# SoC_Power.net
KiCad netlist of a schematic drawn in Altium Designer
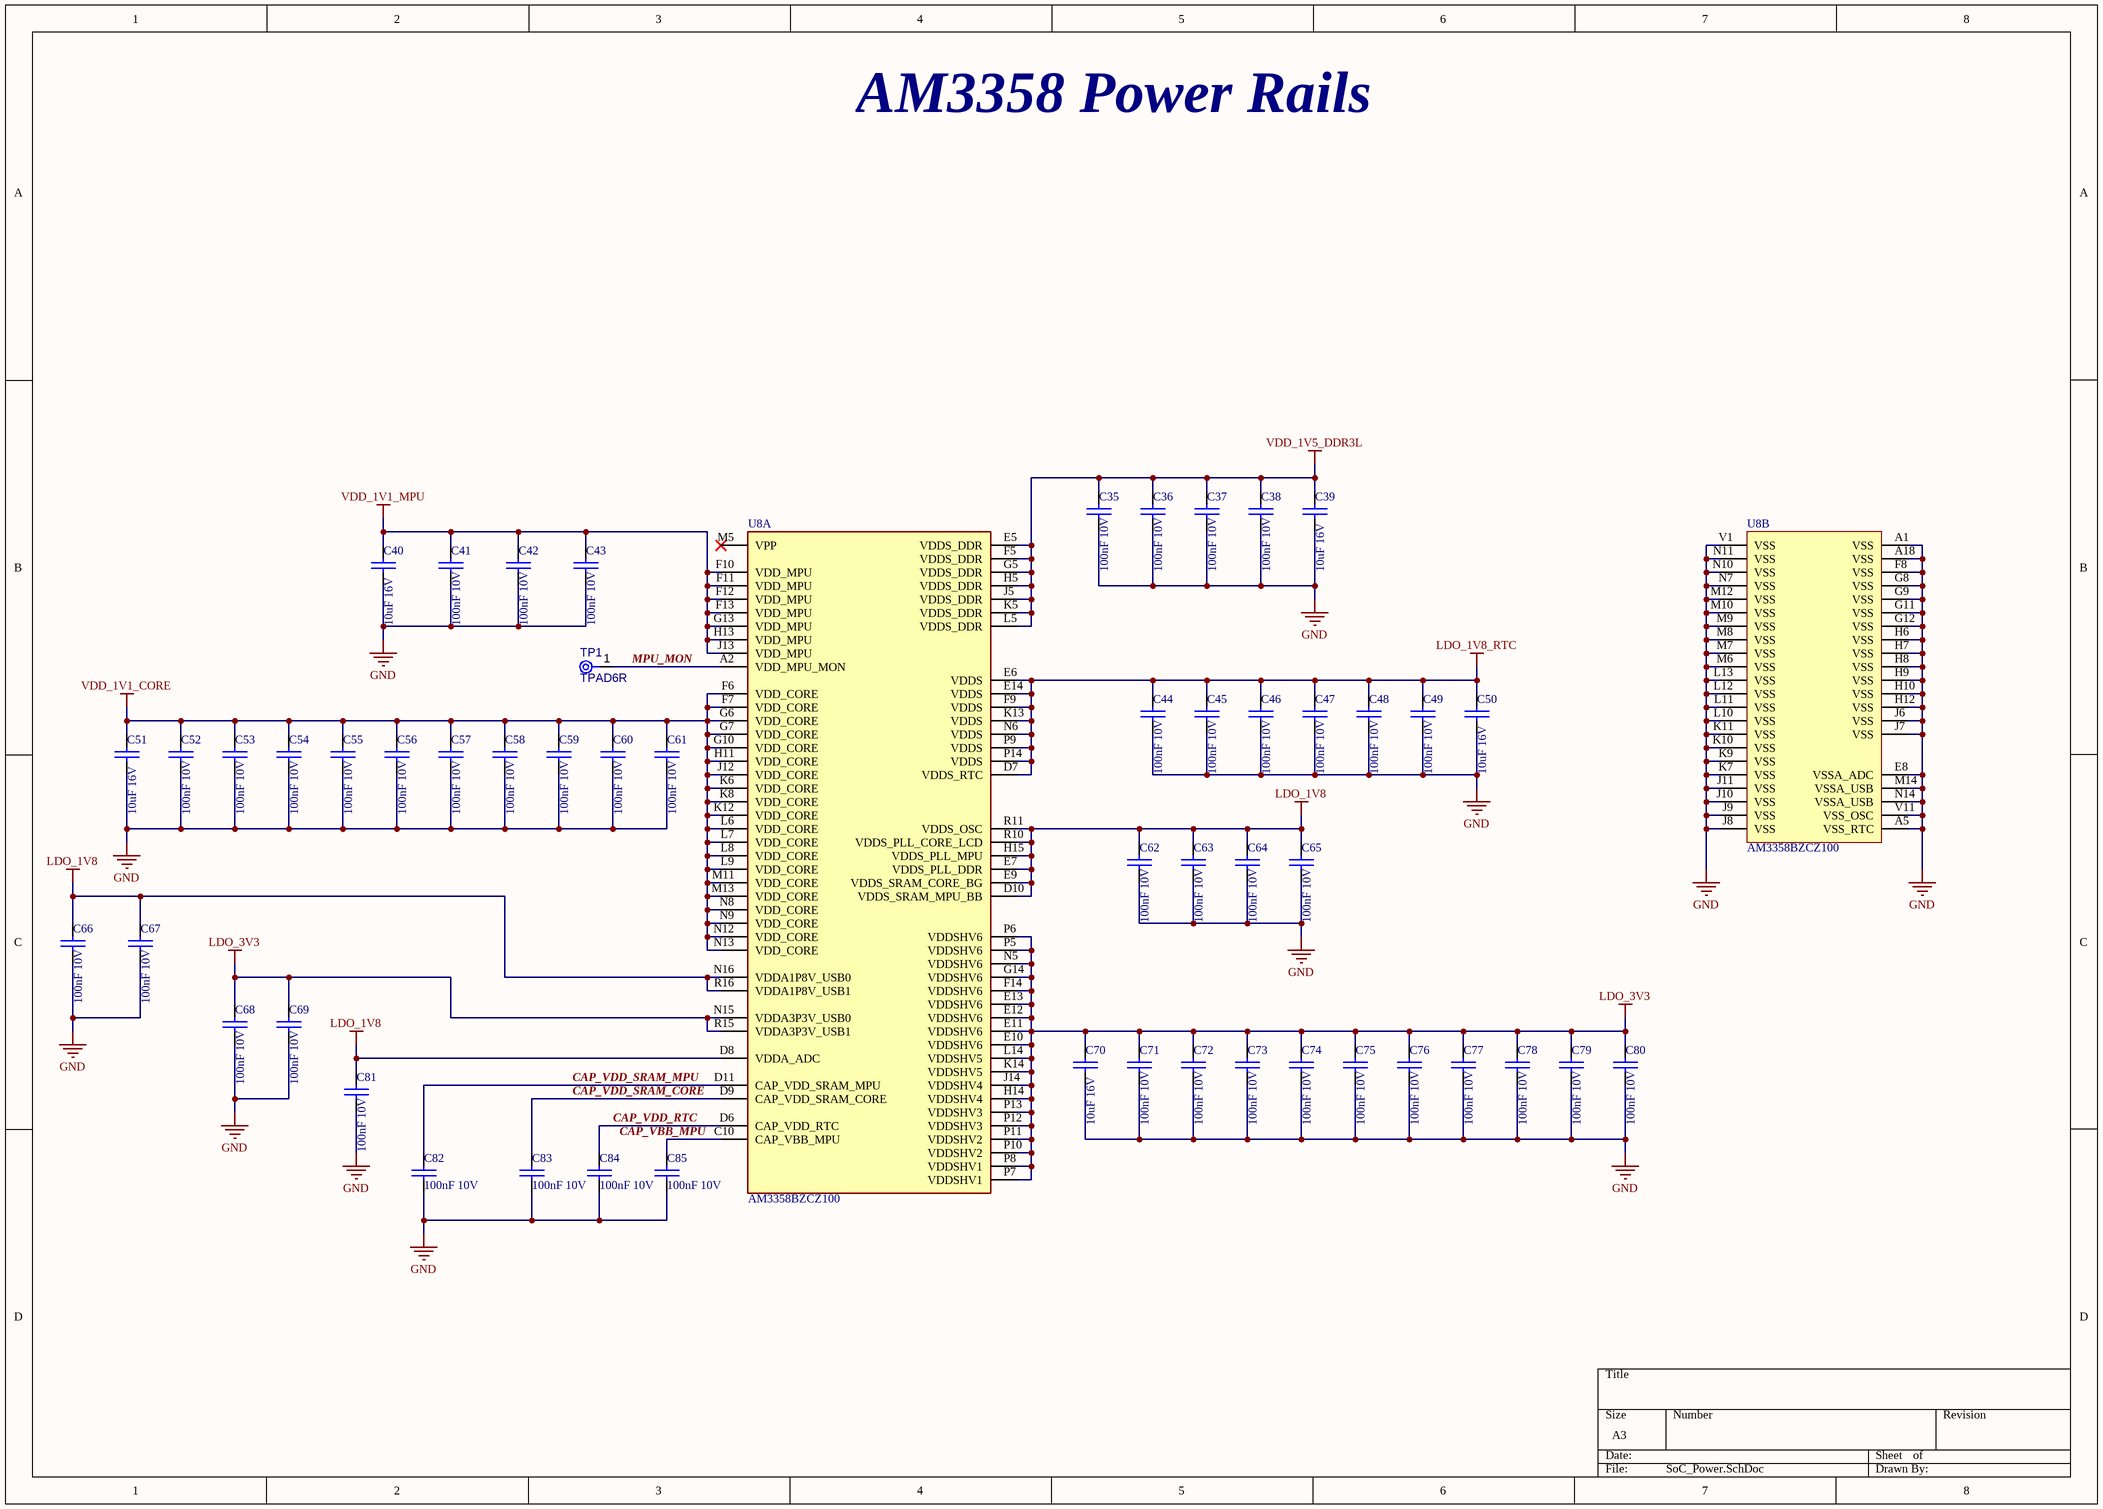
[diagram p0: SoC_Power.SchDoc]

(export (version "E")
  (design (tool "Eeschema 10.0.6"))
  (components
    (comp (ref "C35")
      (value "100nF 10V")
      (footprint "C_0201")
      (description "Capacitor 0201 SMD")
      (libsource (lib "tor1kkLib") (part "C_0201"))
    )
    (comp (ref "C36")
      (value "100nF 10V")
      (footprint "C_0201")
      (description "Capacitor 0201 SMD")
      (libsource (lib "tor1kkLib") (part "C_0201"))
    )
    (comp (ref "C37")
      (value "100nF 10V")
      (footprint "C_0201")
      (description "Capacitor 0201 SMD")
      (libsource (lib "tor1kkLib") (part "C_0201"))
    )
    (comp (ref "C38")
      (value "100nF 10V")
      (footprint "C_0201")
      (description "Capacitor 0201 SMD")
      (libsource (lib "tor1kkLib") (part "C_0201"))
    )
    (comp (ref "C39")
      (value "10uF 16V")
      (footprint "C_0603")
      (description "Capacitor 0603 SMD")
      (libsource (lib "tor1kkLib") (part "C_0603"))
    )
    (comp (ref "C40")
      (value "10uF 16V")
      (footprint "C_0603")
      (description "Capacitor 0603 SMD")
      (libsource (lib "tor1kkLib") (part "C_0603"))
    )
    (comp (ref "C41")
      (value "100nF 10V")
      (footprint "C_0201")
      (description "Capacitor 0201 SMD")
      (libsource (lib "tor1kkLib") (part "C_0201"))
    )
    (comp (ref "C42")
      (value "100nF 10V")
      (footprint "C_0201")
      (description "Capacitor 0201 SMD")
      (libsource (lib "tor1kkLib") (part "C_0201"))
    )
    (comp (ref "C43")
      (value "100nF 10V")
      (footprint "C_0201")
      (description "Capacitor 0201 SMD")
      (libsource (lib "tor1kkLib") (part "C_0201"))
    )
    (comp (ref "C44")
      (value "100nF 10V")
      (footprint "C_0201")
      (description "Capacitor 0201 SMD")
      (libsource (lib "tor1kkLib") (part "C_0201"))
    )
    (comp (ref "C45")
      (value "100nF 10V")
      (footprint "C_0201")
      (description "Capacitor 0201 SMD")
      (libsource (lib "tor1kkLib") (part "C_0201"))
    )
    (comp (ref "C46")
      (value "100nF 10V")
      (footprint "C_0201")
      (description "Capacitor 0201 SMD")
      (libsource (lib "tor1kkLib") (part "C_0201"))
    )
    (comp (ref "C47")
      (value "100nF 10V")
      (footprint "C_0201")
      (description "Capacitor 0201 SMD")
      (libsource (lib "tor1kkLib") (part "C_0201"))
    )
    (comp (ref "C48")
      (value "100nF 10V")
      (footprint "C_0201")
      (description "Capacitor 0201 SMD")
      (libsource (lib "tor1kkLib") (part "C_0201"))
    )
    (comp (ref "C49")
      (value "100nF 10V")
      (footprint "C_0201")
      (description "Capacitor 0201 SMD")
      (libsource (lib "tor1kkLib") (part "C_0201"))
    )
    (comp (ref "C50")
      (value "10uF 16V")
      (footprint "C_0603")
      (description "Capacitor 0603 SMD")
      (libsource (lib "tor1kkLib") (part "C_0603"))
    )
    (comp (ref "C51")
      (value "10uF 16V")
      (footprint "C_0603")
      (description "Capacitor 0603 SMD")
      (libsource (lib "tor1kkLib") (part "C_0603"))
    )
    (comp (ref "C52")
      (value "100nF 10V")
      (footprint "C_0201")
      (description "Capacitor 0201 SMD")
      (libsource (lib "tor1kkLib") (part "C_0201"))
    )
    (comp (ref "C53")
      (value "100nF 10V")
      (footprint "C_0201")
      (description "Capacitor 0201 SMD")
      (libsource (lib "tor1kkLib") (part "C_0201"))
    )
    (comp (ref "C54")
      (value "100nF 10V")
      (footprint "C_0201")
      (description "Capacitor 0201 SMD")
      (libsource (lib "tor1kkLib") (part "C_0201"))
    )
    (comp (ref "C55")
      (value "100nF 10V")
      (footprint "C_0201")
      (description "Capacitor 0201 SMD")
      (libsource (lib "tor1kkLib") (part "C_0201"))
    )
    (comp (ref "C56")
      (value "100nF 10V")
      (footprint "C_0201")
      (description "Capacitor 0201 SMD")
      (libsource (lib "tor1kkLib") (part "C_0201"))
    )
    (comp (ref "C57")
      (value "100nF 10V")
      (footprint "C_0201")
      (description "Capacitor 0201 SMD")
      (libsource (lib "tor1kkLib") (part "C_0201"))
    )
    (comp (ref "C58")
      (value "100nF 10V")
      (footprint "C_0201")
      (description "Capacitor 0201 SMD")
      (libsource (lib "tor1kkLib") (part "C_0201"))
    )
    (comp (ref "C59")
      (value "100nF 10V")
      (footprint "C_0201")
      (description "Capacitor 0201 SMD")
      (libsource (lib "tor1kkLib") (part "C_0201"))
    )
    (comp (ref "C60")
      (value "100nF 10V")
      (footprint "C_0201")
      (description "Capacitor 0201 SMD")
      (libsource (lib "tor1kkLib") (part "C_0201"))
    )
    (comp (ref "C61")
      (value "100nF 10V")
      (footprint "C_0201")
      (description "Capacitor 0201 SMD")
      (libsource (lib "tor1kkLib") (part "C_0201"))
    )
    (comp (ref "C62")
      (value "100nF 10V")
      (footprint "C_0201")
      (description "Capacitor 0201 SMD")
      (libsource (lib "tor1kkLib") (part "C_0201"))
    )
    (comp (ref "C63")
      (value "100nF 10V")
      (footprint "C_0201")
      (description "Capacitor 0201 SMD")
      (libsource (lib "tor1kkLib") (part "C_0201"))
    )
    (comp (ref "C64")
      (value "100nF 10V")
      (footprint "C_0201")
      (description "Capacitor 0201 SMD")
      (libsource (lib "tor1kkLib") (part "C_0201"))
    )
    (comp (ref "C65")
      (value "100nF 10V")
      (footprint "C_0201")
      (description "Capacitor 0201 SMD")
      (libsource (lib "tor1kkLib") (part "C_0201"))
    )
    (comp (ref "C66")
      (value "100nF 10V")
      (footprint "C_0201")
      (description "Capacitor 0201 SMD")
      (libsource (lib "tor1kkLib") (part "C_0201"))
    )
    (comp (ref "C67")
      (value "100nF 10V")
      (footprint "C_0201")
      (description "Capacitor 0201 SMD")
      (libsource (lib "tor1kkLib") (part "C_0201"))
    )
    (comp (ref "C68")
      (value "100nF 10V")
      (footprint "C_0201")
      (description "Capacitor 0201 SMD")
      (libsource (lib "tor1kkLib") (part "C_0201"))
    )
    (comp (ref "C69")
      (value "100nF 10V")
      (footprint "C_0201")
      (description "Capacitor 0201 SMD")
      (libsource (lib "tor1kkLib") (part "C_0201"))
    )
    (comp (ref "C70")
      (value "10uF 16V")
      (footprint "C_0603")
      (description "Capacitor 0603 SMD")
      (libsource (lib "tor1kkLib") (part "C_0603"))
    )
    (comp (ref "C71")
      (value "100nF 10V")
      (footprint "C_0201")
      (description "Capacitor 0201 SMD")
      (libsource (lib "tor1kkLib") (part "C_0201"))
    )
    (comp (ref "C72")
      (value "100nF 10V")
      (footprint "C_0201")
      (description "Capacitor 0201 SMD")
      (libsource (lib "tor1kkLib") (part "C_0201"))
    )
    (comp (ref "C73")
      (value "100nF 10V")
      (footprint "C_0201")
      (description "Capacitor 0201 SMD")
      (libsource (lib "tor1kkLib") (part "C_0201"))
    )
    (comp (ref "C74")
      (value "100nF 10V")
      (footprint "C_0201")
      (description "Capacitor 0201 SMD")
      (libsource (lib "tor1kkLib") (part "C_0201"))
    )
    (comp (ref "C75")
      (value "100nF 10V")
      (footprint "C_0201")
      (description "Capacitor 0201 SMD")
      (libsource (lib "tor1kkLib") (part "C_0201"))
    )
    (comp (ref "C76")
      (value "100nF 10V")
      (footprint "C_0201")
      (description "Capacitor 0201 SMD")
      (libsource (lib "tor1kkLib") (part "C_0201"))
    )
    (comp (ref "C77")
      (value "100nF 10V")
      (footprint "C_0201")
      (description "Capacitor 0201 SMD")
      (libsource (lib "tor1kkLib") (part "C_0201"))
    )
    (comp (ref "C78")
      (value "100nF 10V")
      (footprint "C_0201")
      (description "Capacitor 0201 SMD")
      (libsource (lib "tor1kkLib") (part "C_0201"))
    )
    (comp (ref "C79")
      (value "100nF 10V")
      (footprint "C_0201")
      (description "Capacitor 0201 SMD")
      (libsource (lib "tor1kkLib") (part "C_0201"))
    )
    (comp (ref "C80")
      (value "100nF 10V")
      (footprint "C_0201")
      (description "Capacitor 0201 SMD")
      (libsource (lib "tor1kkLib") (part "C_0201"))
    )
    (comp (ref "C81")
      (value "100nF 10V")
      (footprint "C_0201")
      (description "Capacitor 0201 SMD")
      (libsource (lib "tor1kkLib") (part "C_0201"))
    )
    (comp (ref "C82")
      (value "100nF 10V")
      (footprint "C_0201")
      (description "Capacitor 0201 SMD")
      (libsource (lib "tor1kkLib") (part "C_0201"))
    )
    (comp (ref "C83")
      (value "100nF 10V")
      (footprint "C_0201")
      (description "Capacitor 0201 SMD")
      (libsource (lib "tor1kkLib") (part "C_0201"))
    )
    (comp (ref "C84")
      (value "100nF 10V")
      (footprint "C_0201")
      (description "Capacitor 0201 SMD")
      (libsource (lib "tor1kkLib") (part "C_0201"))
    )
    (comp (ref "C85")
      (value "100nF 10V")
      (footprint "C_0201")
      (description "Capacitor 0201 SMD")
      (libsource (lib "tor1kkLib") (part "C_0201"))
    )
    (comp (ref "TP1")
      (value "TPAD6R")
      (footprint "TP06R")
      (description "0.6mm round")
      (libsource (lib "Viktor Sobetskyi") (part "CMP-001-0001-4"))
    )
    (comp (ref "U8")
      (value "AM3358BZCZ100")
      (footprint "BGA324C80P18X18_1500X1500X140")
      (description "ARM-ASeries 1GHz NFBGA-324 Microcontrollers (MCU/MPU/SOC) ROHS")
      (fields (field (name "MANUFACTURER") "Texas Instruments"))
      (libsource (lib "tor1kkLib") (part "AM3358BZCZ100"))
    )
  )
  (nets
    (net (code "1") (name "/CAP_VBB_MPU") (class "Default")
      (node (ref "C85") (pin "1") (pintype "passive"))
      (node (ref "U8") (pin "C10") (pinfunction "CAP_VBB_MPU_C10") (pintype "power_in"))
    )
    (net (code "2") (name "/CAP_VDD_RTC") (class "Default")
      (node (ref "C84") (pin "1") (pintype "passive"))
      (node (ref "U8") (pin "D6") (pinfunction "CAP_VDD_RTC_D6") (pintype "power_in"))
    )
    (net (code "3") (name "/CAP_VDD_SRAM_CORE") (class "Default")
      (node (ref "C83") (pin "1") (pintype "passive"))
      (node (ref "U8") (pin "D9") (pinfunction "CAP_VDD_SRAM_CORE_D9") (pintype "power_in"))
    )
    (net (code "4") (name "/CAP_VDD_SRAM_MPU") (class "Default")
      (node (ref "C82") (pin "1") (pintype "passive"))
      (node (ref "U8") (pin "D11") (pinfunction "CAP_VDD_SRAM_MPU_D11") (pintype "power_in"))
    )
    (net (code "5") (name "/MPU_MON") (class "Default")
      (node (ref "TP1") (pin "1") (pinfunction "TP_1") (pintype "passive"))
      (node (ref "U8") (pin "A2") (pinfunction "VDD_MPU_MON_A2") (pintype "power_in"))
    )
    (net (code "6") (name "GND") (class "Default")
      (node (ref "C35") (pin "2") (pintype "passive"))
      (node (ref "C36") (pin "2") (pintype "passive"))
      (node (ref "C37") (pin "2") (pintype "passive"))
      (node (ref "C38") (pin "2") (pintype "passive"))
      (node (ref "C39") (pin "2") (pintype "passive"))
      (node (ref "C40") (pin "2") (pintype "passive"))
      (node (ref "C41") (pin "2") (pintype "passive"))
      (node (ref "C42") (pin "2") (pintype "passive"))
      (node (ref "C43") (pin "2") (pintype "passive"))
      (node (ref "C44") (pin "2") (pintype "passive"))
      (node (ref "C45") (pin "2") (pintype "passive"))
      (node (ref "C46") (pin "2") (pintype "passive"))
      (node (ref "C47") (pin "2") (pintype "passive"))
      (node (ref "C48") (pin "2") (pintype "passive"))
      (node (ref "C49") (pin "2") (pintype "passive"))
      (node (ref "C50") (pin "2") (pintype "passive"))
      (node (ref "C51") (pin "2") (pintype "passive"))
      (node (ref "C52") (pin "2") (pintype "passive"))
      (node (ref "C53") (pin "2") (pintype "passive"))
      (node (ref "C54") (pin "2") (pintype "passive"))
      (node (ref "C55") (pin "2") (pintype "passive"))
      (node (ref "C56") (pin "2") (pintype "passive"))
      (node (ref "C57") (pin "2") (pintype "passive"))
      (node (ref "C58") (pin "2") (pintype "passive"))
      (node (ref "C59") (pin "2") (pintype "passive"))
      (node (ref "C60") (pin "2") (pintype "passive"))
      (node (ref "C61") (pin "2") (pintype "passive"))
      (node (ref "C62") (pin "2") (pintype "passive"))
      (node (ref "C63") (pin "2") (pintype "passive"))
      (node (ref "C64") (pin "2") (pintype "passive"))
      (node (ref "C65") (pin "2") (pintype "passive"))
      (node (ref "C66") (pin "2") (pintype "passive"))
      (node (ref "C67") (pin "2") (pintype "passive"))
      (node (ref "C68") (pin "2") (pintype "passive"))
      (node (ref "C69") (pin "2") (pintype "passive"))
      (node (ref "C70") (pin "2") (pintype "passive"))
      (node (ref "C71") (pin "2") (pintype "passive"))
      (node (ref "C72") (pin "2") (pintype "passive"))
      (node (ref "C73") (pin "2") (pintype "passive"))
      (node (ref "C74") (pin "2") (pintype "passive"))
      (node (ref "C75") (pin "2") (pintype "passive"))
      (node (ref "C76") (pin "2") (pintype "passive"))
      (node (ref "C77") (pin "2") (pintype "passive"))
      (node (ref "C78") (pin "2") (pintype "passive"))
      (node (ref "C79") (pin "2") (pintype "passive"))
      (node (ref "C80") (pin "2") (pintype "passive"))
      (node (ref "C81") (pin "2") (pintype "passive"))
      (node (ref "C82") (pin "2") (pintype "passive"))
      (node (ref "C83") (pin "2") (pintype "passive"))
      (node (ref "C84") (pin "2") (pintype "passive"))
      (node (ref "C85") (pin "2") (pintype "passive"))
      (node (ref "U8") (pin "A1") (pinfunction "VSS_A1") (pintype "power_in"))
      (node (ref "U8") (pin "A18") (pinfunction "VSS_A18") (pintype "power_in"))
      (node (ref "U8") (pin "A5") (pinfunction "VSS_RTC_A5") (pintype "power_in"))
      (node (ref "U8") (pin "E8") (pinfunction "VSSA_ADC_E8") (pintype "power_in"))
      (node (ref "U8") (pin "F8") (pinfunction "VSS_F8") (pintype "power_in"))
      (node (ref "U8") (pin "G11") (pinfunction "VSS_G11") (pintype "power_in"))
      (node (ref "U8") (pin "G12") (pinfunction "VSS_G12") (pintype "power_in"))
      (node (ref "U8") (pin "G8") (pinfunction "VSS_G8") (pintype "power_in"))
      (node (ref "U8") (pin "G9") (pinfunction "VSS_G9") (pintype "power_in"))
      (node (ref "U8") (pin "H10") (pinfunction "VSS_H10") (pintype "power_in"))
      (node (ref "U8") (pin "H12") (pinfunction "VSS_H12") (pintype "power_in"))
      (node (ref "U8") (pin "H6") (pinfunction "VSS_H6") (pintype "power_in"))
      (node (ref "U8") (pin "H7") (pinfunction "VSS_H7") (pintype "power_in"))
      (node (ref "U8") (pin "H8") (pinfunction "VSS_H8") (pintype "power_in"))
      (node (ref "U8") (pin "H9") (pinfunction "VSS_H9") (pintype "power_in"))
      (node (ref "U8") (pin "J10") (pinfunction "VSS_J10") (pintype "power_in"))
      (node (ref "U8") (pin "J11") (pinfunction "VSS_J11") (pintype "power_in"))
      (node (ref "U8") (pin "J6") (pinfunction "VSS_J6") (pintype "power_in"))
      (node (ref "U8") (pin "J7") (pinfunction "VSS_J7") (pintype "power_in"))
      (node (ref "U8") (pin "J8") (pinfunction "VSS_J8") (pintype "power_in"))
      (node (ref "U8") (pin "J9") (pinfunction "VSS_J9") (pintype "power_in"))
      (node (ref "U8") (pin "K10") (pinfunction "VSS_K10") (pintype "power_in"))
      (node (ref "U8") (pin "K11") (pinfunction "VSS_K11") (pintype "power_in"))
      (node (ref "U8") (pin "K7") (pinfunction "VSS_K7") (pintype "power_in"))
      (node (ref "U8") (pin "K9") (pinfunction "VSS_K9") (pintype "power_in"))
      (node (ref "U8") (pin "L10") (pinfunction "VSS_L10") (pintype "power_in"))
      (node (ref "U8") (pin "L11") (pinfunction "VSS_L11") (pintype "power_in"))
      (node (ref "U8") (pin "L12") (pinfunction "VSS_L12") (pintype "power_in"))
      (node (ref "U8") (pin "L13") (pinfunction "VSS_L13") (pintype "power_in"))
      (node (ref "U8") (pin "M10") (pinfunction "VSS_M10") (pintype "power_in"))
      (node (ref "U8") (pin "M12") (pinfunction "VSS_M12") (pintype "power_in"))
      (node (ref "U8") (pin "M14") (pinfunction "VSSA_USB_M14") (pintype "power_in"))
      (node (ref "U8") (pin "M6") (pinfunction "VSS_M6") (pintype "power_in"))
      (node (ref "U8") (pin "M7") (pinfunction "VSS_M7") (pintype "power_in"))
      (node (ref "U8") (pin "M8") (pinfunction "VSS_M8") (pintype "power_in"))
      (node (ref "U8") (pin "M9") (pinfunction "VSS_M9") (pintype "power_in"))
      (node (ref "U8") (pin "N10") (pinfunction "VSS_N10") (pintype "power_in"))
      (node (ref "U8") (pin "N11") (pinfunction "VSS_N11") (pintype "power_in"))
      (node (ref "U8") (pin "N14") (pinfunction "VSSA_USB_N14") (pintype "power_in"))
      (node (ref "U8") (pin "N7") (pinfunction "VSS_N7") (pintype "power_in"))
      (node (ref "U8") (pin "V1") (pinfunction "VSS_V1") (pintype "power_in"))
      (node (ref "U8") (pin "V11") (pinfunction "VSS_OSC_V11") (pintype "power_in"))
    )
    (net (code "7") (name "LDO_1V8") (class "Default")
      (node (ref "C62") (pin "1") (pintype "passive"))
      (node (ref "C63") (pin "1") (pintype "passive"))
      (node (ref "C64") (pin "1") (pintype "passive"))
      (node (ref "C65") (pin "1") (pintype "passive"))
      (node (ref "C66") (pin "1") (pintype "passive"))
      (node (ref "C67") (pin "1") (pintype "passive"))
      (node (ref "C81") (pin "1") (pintype "passive"))
      (node (ref "U8") (pin "D10") (pinfunction "VDDS_SRAM_MPU_BB_D10") (pintype "power_in"))
      (node (ref "U8") (pin "D8") (pinfunction "VDDA_ADC_D8") (pintype "power_in"))
      (node (ref "U8") (pin "E7") (pinfunction "VDDS_PLL_DDR_E7") (pintype "power_in"))
      (node (ref "U8") (pin "E9") (pinfunction "VDDS_SRAM_CORE_BG_E9") (pintype "power_in"))
      (node (ref "U8") (pin "H15") (pinfunction "VDDS_PLL_MPU_H15") (pintype "power_in"))
      (node (ref "U8") (pin "N16") (pinfunction "VDDA1P8V_USB0_N16") (pintype "power_in"))
      (node (ref "U8") (pin "R10") (pinfunction "VDDS_PLL_CORE_LCD_R10") (pintype "power_in"))
      (node (ref "U8") (pin "R11") (pinfunction "VDDS_OSC_R11") (pintype "power_in"))
      (node (ref "U8") (pin "R16") (pinfunction "VDDA1P8V_USB1_R16") (pintype "power_in"))
    )
    (net (code "8") (name "LDO_1V8_RTC") (class "Default")
      (node (ref "C44") (pin "1") (pintype "passive"))
      (node (ref "C45") (pin "1") (pintype "passive"))
      (node (ref "C46") (pin "1") (pintype "passive"))
      (node (ref "C47") (pin "1") (pintype "passive"))
      (node (ref "C48") (pin "1") (pintype "passive"))
      (node (ref "C49") (pin "1") (pintype "passive"))
      (node (ref "C50") (pin "1") (pintype "passive"))
      (node (ref "U8") (pin "D7") (pinfunction "VDDS_RTC_D7") (pintype "power_in"))
      (node (ref "U8") (pin "E14") (pinfunction "VDDS_E14") (pintype "power_in"))
      (node (ref "U8") (pin "E6") (pinfunction "VDDS_E6") (pintype "power_in"))
      (node (ref "U8") (pin "F9") (pinfunction "VDDS_F9") (pintype "power_in"))
      (node (ref "U8") (pin "K13") (pinfunction "VDDS_K13") (pintype "power_in"))
      (node (ref "U8") (pin "N6") (pinfunction "VDDS_N6") (pintype "power_in"))
      (node (ref "U8") (pin "P14") (pinfunction "VDDS_P14") (pintype "power_in"))
      (node (ref "U8") (pin "P9") (pinfunction "VDDS_P9") (pintype "power_in"))
    )
    (net (code "9") (name "LDO_3V3") (class "Default")
      (node (ref "C68") (pin "1") (pintype "passive"))
      (node (ref "C69") (pin "1") (pintype "passive"))
      (node (ref "C70") (pin "1") (pintype "passive"))
      (node (ref "C71") (pin "1") (pintype "passive"))
      (node (ref "C72") (pin "1") (pintype "passive"))
      (node (ref "C73") (pin "1") (pintype "passive"))
      (node (ref "C74") (pin "1") (pintype "passive"))
      (node (ref "C75") (pin "1") (pintype "passive"))
      (node (ref "C76") (pin "1") (pintype "passive"))
      (node (ref "C77") (pin "1") (pintype "passive"))
      (node (ref "C78") (pin "1") (pintype "passive"))
      (node (ref "C79") (pin "1") (pintype "passive"))
      (node (ref "C80") (pin "1") (pintype "passive"))
      (node (ref "U8") (pin "E10") (pinfunction "VDDSHV6_E10") (pintype "power_in"))
      (node (ref "U8") (pin "E11") (pinfunction "VDDSHV6_E11") (pintype "power_in"))
      (node (ref "U8") (pin "E12") (pinfunction "VDDSHV6_E12") (pintype "power_in"))
      (node (ref "U8") (pin "E13") (pinfunction "VDDSHV6_E13") (pintype "power_in"))
      (node (ref "U8") (pin "F14") (pinfunction "VDDSHV6_F14") (pintype "power_in"))
      (node (ref "U8") (pin "G14") (pinfunction "VDDSHV6_G14") (pintype "power_in"))
      (node (ref "U8") (pin "H14") (pinfunction "VDDSHV4_H14") (pintype "power_in"))
      (node (ref "U8") (pin "J14") (pinfunction "VDDSHV4_J14") (pintype "power_in"))
      (node (ref "U8") (pin "K14") (pinfunction "VDDSHV5_K14") (pintype "power_in"))
      (node (ref "U8") (pin "L14") (pinfunction "VDDSHV5_L14") (pintype "power_in"))
      (node (ref "U8") (pin "N15") (pinfunction "VDDA3P3V_USB0_N15") (pintype "power_in"))
      (node (ref "U8") (pin "N5") (pinfunction "VDDSHV6_N5") (pintype "power_in"))
      (node (ref "U8") (pin "P10") (pinfunction "VDDSHV2_P10") (pintype "power_in"))
      (node (ref "U8") (pin "P11") (pinfunction "VDDSHV2_P11") (pintype "power_in"))
      (node (ref "U8") (pin "P12") (pinfunction "VDDSHV3_P12") (pintype "power_in"))
      (node (ref "U8") (pin "P13") (pinfunction "VDDSHV3_P13") (pintype "power_in"))
      (node (ref "U8") (pin "P5") (pinfunction "VDDSHV6_P5") (pintype "power_in"))
      (node (ref "U8") (pin "P6") (pinfunction "VDDSHV6_P6") (pintype "power_in"))
      (node (ref "U8") (pin "P7") (pinfunction "VDDSHV1_P7") (pintype "power_in"))
      (node (ref "U8") (pin "P8") (pinfunction "VDDSHV1_P8") (pintype "power_in"))
      (node (ref "U8") (pin "R15") (pinfunction "VDDA3P3V_USB1_R15") (pintype "power_in"))
    )
    (net (code "10") (name "VDD_1V1_CORE") (class "Default")
      (node (ref "C51") (pin "1") (pintype "passive"))
      (node (ref "C52") (pin "1") (pintype "passive"))
      (node (ref "C53") (pin "1") (pintype "passive"))
      (node (ref "C54") (pin "1") (pintype "passive"))
      (node (ref "C55") (pin "1") (pintype "passive"))
      (node (ref "C56") (pin "1") (pintype "passive"))
      (node (ref "C57") (pin "1") (pintype "passive"))
      (node (ref "C58") (pin "1") (pintype "passive"))
      (node (ref "C59") (pin "1") (pintype "passive"))
      (node (ref "C60") (pin "1") (pintype "passive"))
      (node (ref "C61") (pin "1") (pintype "passive"))
      (node (ref "U8") (pin "F6") (pinfunction "VDD_CORE_F6") (pintype "power_in"))
      (node (ref "U8") (pin "F7") (pinfunction "VDD_CORE_F7") (pintype "power_in"))
      (node (ref "U8") (pin "G10") (pinfunction "VDD_CORE_G10") (pintype "power_in"))
      (node (ref "U8") (pin "G6") (pinfunction "VDD_CORE_G6") (pintype "power_in"))
      (node (ref "U8") (pin "G7") (pinfunction "VDD_CORE_G7") (pintype "power_in"))
      (node (ref "U8") (pin "H11") (pinfunction "VDD_CORE_H11") (pintype "power_in"))
      (node (ref "U8") (pin "J12") (pinfunction "VDD_CORE_J12") (pintype "power_in"))
      (node (ref "U8") (pin "K12") (pinfunction "VDD_CORE_K12") (pintype "power_in"))
      (node (ref "U8") (pin "K6") (pinfunction "VDD_CORE_K6") (pintype "power_in"))
      (node (ref "U8") (pin "K8") (pinfunction "VDD_CORE_K8") (pintype "power_in"))
      (node (ref "U8") (pin "L6") (pinfunction "VDD_CORE_L6") (pintype "power_in"))
      (node (ref "U8") (pin "L7") (pinfunction "VDD_CORE_L7") (pintype "power_in"))
      (node (ref "U8") (pin "L8") (pinfunction "VDD_CORE_L8") (pintype "power_in"))
      (node (ref "U8") (pin "L9") (pinfunction "VDD_CORE_L9") (pintype "power_in"))
      (node (ref "U8") (pin "M11") (pinfunction "VDD_CORE_M11") (pintype "power_in"))
      (node (ref "U8") (pin "M13") (pinfunction "VDD_CORE_M13") (pintype "power_in"))
      (node (ref "U8") (pin "N12") (pinfunction "VDD_CORE_N12") (pintype "power_in"))
      (node (ref "U8") (pin "N13") (pinfunction "VDD_CORE_N13") (pintype "power_in"))
      (node (ref "U8") (pin "N8") (pinfunction "VDD_CORE_N8") (pintype "power_in"))
      (node (ref "U8") (pin "N9") (pinfunction "VDD_CORE_N9") (pintype "power_in"))
    )
    (net (code "11") (name "VDD_1V1_MPU") (class "Default")
      (node (ref "C40") (pin "1") (pintype "passive"))
      (node (ref "C41") (pin "1") (pintype "passive"))
      (node (ref "C42") (pin "1") (pintype "passive"))
      (node (ref "C43") (pin "1") (pintype "passive"))
      (node (ref "U8") (pin "F10") (pinfunction "VDD_MPU_F10") (pintype "power_in"))
      (node (ref "U8") (pin "F11") (pinfunction "VDD_MPU_F11") (pintype "power_in"))
      (node (ref "U8") (pin "F12") (pinfunction "VDD_MPU_F12") (pintype "power_in"))
      (node (ref "U8") (pin "F13") (pinfunction "VDD_MPU_F13") (pintype "power_in"))
      (node (ref "U8") (pin "G13") (pinfunction "VDD_MPU_G13") (pintype "power_in"))
      (node (ref "U8") (pin "H13") (pinfunction "VDD_MPU_H13") (pintype "power_in"))
      (node (ref "U8") (pin "J13") (pinfunction "VDD_MPU_J13") (pintype "power_in"))
    )
    (net (code "12") (name "VDD_1V5_DDR3L") (class "Default")
      (node (ref "C35") (pin "1") (pintype "passive"))
      (node (ref "C36") (pin "1") (pintype "passive"))
      (node (ref "C37") (pin "1") (pintype "passive"))
      (node (ref "C38") (pin "1") (pintype "passive"))
      (node (ref "C39") (pin "1") (pintype "passive"))
      (node (ref "U8") (pin "E5") (pinfunction "VDDS_DDR_E5") (pintype "power_in"))
      (node (ref "U8") (pin "F5") (pinfunction "VDDS_DDR_F5") (pintype "power_in"))
      (node (ref "U8") (pin "G5") (pinfunction "VDDS_DDR_G5") (pintype "power_in"))
      (node (ref "U8") (pin "H5") (pinfunction "VDDS_DDR_H5") (pintype "power_in"))
      (node (ref "U8") (pin "J5") (pinfunction "VDDS_DDR_J5") (pintype "power_in"))
      (node (ref "U8") (pin "K5") (pinfunction "VDDS_DDR_K5") (pintype "power_in"))
      (node (ref "U8") (pin "L5") (pinfunction "VDDS_DDR_L5") (pintype "power_in"))
    )
    (net (code "13") (name "unconnected-(U8A-VPP-PadM5)") (class "Default")
      (node (ref "U8") (pin "M5") (pinfunction "VPP_M5") (pintype "power_in+no_connect"))
    )
  )
)
